# LED.net
KiCad netlist of a schematic drawn in EAGLE
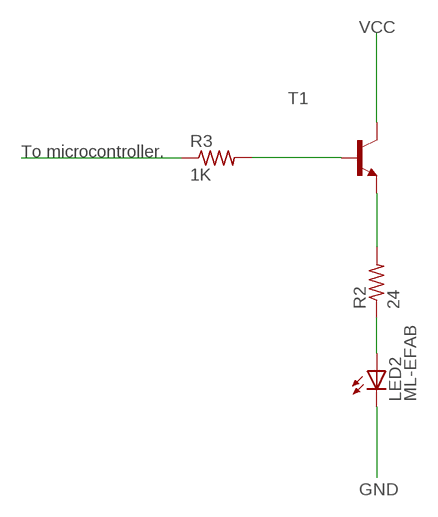
[diagram p0: schematic, sheet 1]

(export (version "E")
  (design (tool "Eeschema 10.0.6"))
  (components
    (comp (ref "LED2")
      (value "ML-EFAB")
      (footprint "eagle-import:ML-E-FAB")
      (libsource (lib "eagle-import") (part "ML-EFAB"))
    )
    (comp (ref "R2")
      (value "24")
      (footprint "eagle-import:R1206")
      (libsource (lib "eagle-import") (part "R-US_R1206"))
    )
    (comp (ref "R3")
      (value "1K")
      (footprint "eagle-import:R1206")
      (libsource (lib "eagle-import") (part "R-US_R1206"))
    )
    (comp (ref "T1")
      (value "MMBT3904LT1-NPN-SOT23-BEC")
      (footprint "eagle-import:SOT23-BEC")
      (libsource (lib "eagle-import") (part "-NPN-SOT23-BECMMBT3904LT1"))
    )
  )
  (nets
    (net (code "1") (name "/GND") (class "Default")
      (node (ref "LED2") (pin "C@1") (pinfunction "C_C@1") (pintype "passive"))
    )
    (net (code "2") (name "/VCC") (class "Default")
      (node (ref "T1") (pin "C") (pinfunction "C_C") (pintype "passive"))
    )
    (net (code "3") (name "Net-(LED2A-A-PadA@1)") (class "Default")
      (node (ref "LED2") (pin "A@1") (pinfunction "A_A@1") (pintype "passive"))
      (node (ref "R2") (pin "1") (pinfunction "1_1") (pintype "passive"))
    )
    (net (code "4") (name "Net-(R2-Pad2)") (class "Default")
      (node (ref "R2") (pin "2") (pinfunction "2_2") (pintype "passive"))
      (node (ref "T1") (pin "E") (pinfunction "E_E") (pintype "passive"))
    )
    (net (code "5") (name "Net-(R3-Pad2)") (class "Default")
      (node (ref "R3") (pin "2") (pinfunction "2_2") (pintype "passive"))
      (node (ref "T1") (pin "B") (pinfunction "B_B") (pintype "passive"))
    )
    (net (code "6") (name "unconnected-(LED2A-A-PadA@2)") (class "Default")
      (node (ref "LED2") (pin "A@2") (pinfunction "A_A@2") (pintype "passive"))
    )
    (net (code "7") (name "unconnected-(LED2A-C-PadC@2)") (class "Default")
      (node (ref "LED2") (pin "C@2") (pinfunction "C_C@2") (pintype "passive"))
    )
    (net (code "8") (name "unconnected-(R3-Pad1)") (class "Default")
      (node (ref "R3") (pin "1") (pinfunction "1_1") (pintype "passive"))
    )
  )
)
